# GPIO.net
KiCad netlist of a schematic drawn in Altium Designer
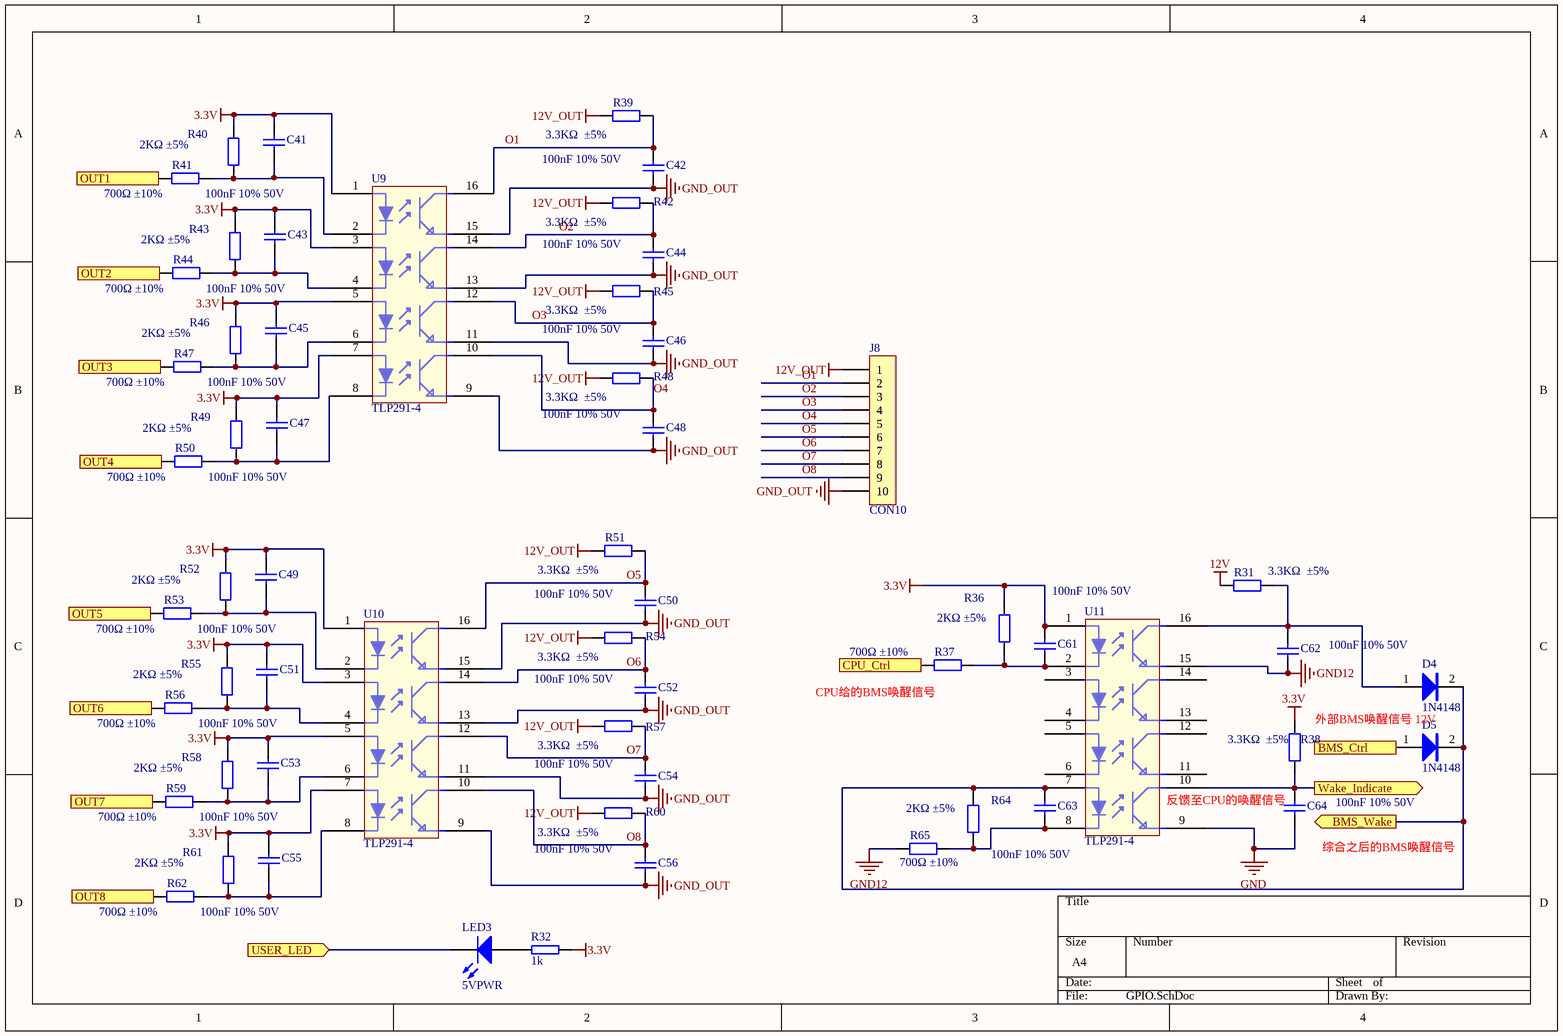
[diagram p0: GPIO.SchDoc]

(export (version "E")
  (design (tool "Eeschema 10.0.6"))
  (components
    (comp (ref "C41")
      (value "100nF 10% 50V")
      (footprint "0603_C")
      (description "贴片电容")
      (libsource (lib "Miscellaneous Devices LC") (part "0603 1nF (102) 10% 50V"))
    )
    (comp (ref "C42")
      (value "100nF 10% 50V")
      (footprint "0603_C")
      (description "贴片电容")
      (libsource (lib "Miscellaneous Devices LC") (part "0603 1nF (102) 10% 50V"))
    )
    (comp (ref "C43")
      (value "100nF 10% 50V")
      (footprint "0603_C")
      (description "贴片电容")
      (libsource (lib "Miscellaneous Devices LC") (part "0603 1nF (102) 10% 50V"))
    )
    (comp (ref "C44")
      (value "100nF 10% 50V")
      (footprint "0603_C")
      (description "贴片电容")
      (libsource (lib "Miscellaneous Devices LC") (part "0603 1nF (102) 10% 50V"))
    )
    (comp (ref "C45")
      (value "100nF 10% 50V")
      (footprint "0603_C")
      (description "贴片电容")
      (libsource (lib "Miscellaneous Devices LC") (part "0603 1nF (102) 10% 50V"))
    )
    (comp (ref "C46")
      (value "100nF 10% 50V")
      (footprint "0603_C")
      (description "贴片电容")
      (libsource (lib "Miscellaneous Devices LC") (part "0603 1nF (102) 10% 50V"))
    )
    (comp (ref "C47")
      (value "100nF 10% 50V")
      (footprint "0603_C")
      (description "贴片电容")
      (libsource (lib "Miscellaneous Devices LC") (part "0603 1nF (102) 10% 50V"))
    )
    (comp (ref "C48")
      (value "100nF 10% 50V")
      (footprint "0603_C")
      (description "贴片电容")
      (libsource (lib "Miscellaneous Devices LC") (part "0603 1nF (102) 10% 50V"))
    )
    (comp (ref "C49")
      (value "100nF 10% 50V")
      (footprint "0603_C")
      (description "贴片电容")
      (libsource (lib "Miscellaneous Devices LC") (part "0603 1nF (102) 10% 50V"))
    )
    (comp (ref "C50")
      (value "100nF 10% 50V")
      (footprint "0603_C")
      (description "贴片电容")
      (libsource (lib "Miscellaneous Devices LC") (part "0603 1nF (102) 10% 50V"))
    )
    (comp (ref "C51")
      (value "100nF 10% 50V")
      (footprint "0603_C")
      (description "贴片电容")
      (libsource (lib "Miscellaneous Devices LC") (part "0603 1nF (102) 10% 50V"))
    )
    (comp (ref "C52")
      (value "100nF 10% 50V")
      (footprint "0603_C")
      (description "贴片电容")
      (libsource (lib "Miscellaneous Devices LC") (part "0603 1nF (102) 10% 50V"))
    )
    (comp (ref "C53")
      (value "100nF 10% 50V")
      (footprint "0603_C")
      (description "贴片电容")
      (libsource (lib "Miscellaneous Devices LC") (part "0603 1nF (102) 10% 50V"))
    )
    (comp (ref "C54")
      (value "100nF 10% 50V")
      (footprint "0603_C")
      (description "贴片电容")
      (libsource (lib "Miscellaneous Devices LC") (part "0603 1nF (102) 10% 50V"))
    )
    (comp (ref "C55")
      (value "100nF 10% 50V")
      (footprint "0603_C")
      (description "贴片电容")
      (libsource (lib "Miscellaneous Devices LC") (part "0603 1nF (102) 10% 50V"))
    )
    (comp (ref "C56")
      (value "100nF 10% 50V")
      (footprint "0603_C")
      (description "贴片电容")
      (libsource (lib "Miscellaneous Devices LC") (part "0603 1nF (102) 10% 50V"))
    )
    (comp (ref "C61")
      (value "100nF 10% 50V")
      (footprint "0603_C")
      (description "贴片电容")
      (libsource (lib "Miscellaneous Devices LC") (part "0603 1nF (102) 10% 50V"))
    )
    (comp (ref "C62")
      (value "100nF 10% 50V")
      (footprint "0603_C")
      (description "贴片电容")
      (libsource (lib "Miscellaneous Devices LC") (part "0603 1nF (102) 10% 50V"))
    )
    (comp (ref "C63")
      (value "100nF 10% 50V")
      (footprint "0603_C")
      (description "贴片电容")
      (libsource (lib "Miscellaneous Devices LC") (part "0603 1nF (102) 10% 50V"))
    )
    (comp (ref "C64")
      (value "100nF 10% 50V")
      (footprint "0603_C")
      (description "贴片电容")
      (libsource (lib "Miscellaneous Devices LC") (part "0603 1nF (102) 10% 50V"))
    )
    (comp (ref "D4") (value "1N4148") (footprint "SOD-323") (libsource (lib "CORE") (part "SS34")))
    (comp (ref "D5") (value "1N4148") (footprint "SOD-323") (libsource (lib "CORE") (part "SS34")))
    (comp (ref "J8") (value "CON10") (footprint "XH2.54-SMD-5*2P") (libsource (lib "常用元件库") (part "CON10")))
    (comp (ref "LED3")
      (value "5VPWR")
      (footprint "LED")
      (description "Typical RED, GREEN, YELLOW, AMBER GaAs LED")
      (fields (field (name "PUBLISHER") "Altium Limited"))
      (libsource (lib "CORE") (part "LED2"))
    )
    (comp (ref "R31")
      (value "3.3KΩ  ±5%")
      (footprint "0603_R")
      (description "贴片电阻")
      (libsource (lib "") (part "0603 3.3KΩ (3301) 1%_1"))
    )
    (comp (ref "R32") (value "1k") (footprint "0603_R") (libsource (lib "EC20-北极芯") (part "RES")))
    (comp (ref "R36")
      (value "2KΩ ±5%")
      (footprint "0603_R")
      (description "贴片电阻")
      (libsource (lib "Miscellaneous Devices LC") (part "0603 2KΩ (2001) 1%"))
    )
    (comp (ref "R37")
      (value "700Ω ±10%")
      (footprint "0603_R")
      (description "贴片电阻")
      (libsource (lib "Miscellaneous Devices LC") (part "0603 5.6KΩ (5601) 1%"))
    )
    (comp (ref "R38")
      (value "3.3KΩ  ±5%")
      (footprint "0603_R")
      (description "贴片电阻")
      (libsource (lib "Miscellaneous Devices LC") (part "0603 3.3KΩ (3301) 1%"))
    )
    (comp (ref "R39")
      (value "3.3KΩ  ±5%")
      (footprint "0603_R")
      (description "贴片电阻")
      (libsource (lib "") (part "0603 3.3KΩ (3301) 1%_1"))
    )
    (comp (ref "R40")
      (value "2KΩ ±5%")
      (footprint "0603_R")
      (description "贴片电阻")
      (libsource (lib "Miscellaneous Devices LC") (part "0603 2KΩ (2001) 1%"))
    )
    (comp (ref "R41")
      (value "700Ω ±10%")
      (footprint "0603_R")
      (description "贴片电阻")
      (libsource (lib "Miscellaneous Devices LC") (part "0603 5.6KΩ (5601) 1%"))
    )
    (comp (ref "R42")
      (value "3.3KΩ  ±5%")
      (footprint "0603_R")
      (description "贴片电阻")
      (libsource (lib "") (part "0603 3.3KΩ (3301) 1%_1"))
    )
    (comp (ref "R43")
      (value "2KΩ ±5%")
      (footprint "0603_R")
      (description "贴片电阻")
      (libsource (lib "Miscellaneous Devices LC") (part "0603 2KΩ (2001) 1%"))
    )
    (comp (ref "R44")
      (value "700Ω ±10%")
      (footprint "0603_R")
      (description "贴片电阻")
      (libsource (lib "Miscellaneous Devices LC") (part "0603 5.6KΩ (5601) 1%"))
    )
    (comp (ref "R45")
      (value "3.3KΩ  ±5%")
      (footprint "0603_R")
      (description "贴片电阻")
      (libsource (lib "") (part "0603 3.3KΩ (3301) 1%_1"))
    )
    (comp (ref "R46")
      (value "2KΩ ±5%")
      (footprint "0603_R")
      (description "贴片电阻")
      (libsource (lib "Miscellaneous Devices LC") (part "0603 2KΩ (2001) 1%"))
    )
    (comp (ref "R47")
      (value "700Ω ±10%")
      (footprint "0603_R")
      (description "贴片电阻")
      (libsource (lib "Miscellaneous Devices LC") (part "0603 5.6KΩ (5601) 1%"))
    )
    (comp (ref "R48")
      (value "3.3KΩ  ±5%")
      (footprint "0603_R")
      (description "贴片电阻")
      (libsource (lib "") (part "0603 3.3KΩ (3301) 1%_1"))
    )
    (comp (ref "R49")
      (value "2KΩ ±5%")
      (footprint "0603_R")
      (description "贴片电阻")
      (libsource (lib "Miscellaneous Devices LC") (part "0603 2KΩ (2001) 1%"))
    )
    (comp (ref "R50")
      (value "700Ω ±10%")
      (footprint "0603_R")
      (description "贴片电阻")
      (libsource (lib "Miscellaneous Devices LC") (part "0603 5.6KΩ (5601) 1%"))
    )
    (comp (ref "R51")
      (value "3.3KΩ  ±5%")
      (footprint "0603_R")
      (description "贴片电阻")
      (libsource (lib "") (part "0603 3.3KΩ (3301) 1%_1"))
    )
    (comp (ref "R52")
      (value "2KΩ ±5%")
      (footprint "0603_R")
      (description "贴片电阻")
      (libsource (lib "Miscellaneous Devices LC") (part "0603 2KΩ (2001) 1%"))
    )
    (comp (ref "R53")
      (value "700Ω ±10%")
      (footprint "0603_R")
      (description "贴片电阻")
      (libsource (lib "Miscellaneous Devices LC") (part "0603 5.6KΩ (5601) 1%"))
    )
    (comp (ref "R54")
      (value "3.3KΩ  ±5%")
      (footprint "0603_R")
      (description "贴片电阻")
      (libsource (lib "") (part "0603 3.3KΩ (3301) 1%_1"))
    )
    (comp (ref "R55")
      (value "2KΩ ±5%")
      (footprint "0603_R")
      (description "贴片电阻")
      (libsource (lib "Miscellaneous Devices LC") (part "0603 2KΩ (2001) 1%"))
    )
    (comp (ref "R56")
      (value "700Ω ±10%")
      (footprint "0603_R")
      (description "贴片电阻")
      (libsource (lib "Miscellaneous Devices LC") (part "0603 5.6KΩ (5601) 1%"))
    )
    (comp (ref "R57")
      (value "3.3KΩ  ±5%")
      (footprint "0603_R")
      (description "贴片电阻")
      (libsource (lib "") (part "0603 3.3KΩ (3301) 1%_1"))
    )
    (comp (ref "R58")
      (value "2KΩ ±5%")
      (footprint "0603_R")
      (description "贴片电阻")
      (libsource (lib "Miscellaneous Devices LC") (part "0603 2KΩ (2001) 1%"))
    )
    (comp (ref "R59")
      (value "700Ω ±10%")
      (footprint "0603_R")
      (description "贴片电阻")
      (libsource (lib "Miscellaneous Devices LC") (part "0603 5.6KΩ (5601) 1%"))
    )
    (comp (ref "R60")
      (value "3.3KΩ  ±5%")
      (footprint "0603_R")
      (description "贴片电阻")
      (libsource (lib "") (part "0603 3.3KΩ (3301) 1%_1"))
    )
    (comp (ref "R61")
      (value "2KΩ ±5%")
      (footprint "0603_R")
      (description "贴片电阻")
      (libsource (lib "Miscellaneous Devices LC") (part "0603 2KΩ (2001) 1%"))
    )
    (comp (ref "R62")
      (value "700Ω ±10%")
      (footprint "0603_R")
      (description "贴片电阻")
      (libsource (lib "Miscellaneous Devices LC") (part "0603 5.6KΩ (5601) 1%"))
    )
    (comp (ref "R64")
      (value "2KΩ ±5%")
      (footprint "0603_R")
      (description "贴片电阻")
      (libsource (lib "Miscellaneous Devices LC") (part "0603 2KΩ (2001) 1%"))
    )
    (comp (ref "R65")
      (value "700Ω ±10%")
      (footprint "0603_R")
      (description "贴片电阻")
      (libsource (lib "Miscellaneous Devices LC") (part "0603 5.6KΩ (5601) 1%"))
    )
    (comp (ref "U9")
      (value "TLP291-4")
      (footprint "SOP16_M")
      (description "东芝四通道光耦 SOP16")
      (libsource (lib "LINXUE") (part "PS2801"))
    )
    (comp (ref "U10")
      (value "TLP291-4")
      (footprint "SOP16_M")
      (description "东芝四通道光耦 SOP16")
      (libsource (lib "LINXUE") (part "PS2801"))
    )
    (comp (ref "U11")
      (value "TLP291-4")
      (footprint "SOP16_M")
      (description "东芝四通道光耦 SOP16")
      (libsource (lib "LINXUE") (part "PS2801"))
    )
  )
  (nets
    (net (code "1") (name "/BMS_Ctrl") (class "Default")
      (node (ref "D5") (pin "1") (pinfunction "1_1") (pintype "passive"))
    )
    (net (code "2") (name "/BMS_Wake") (class "Default")
      (node (ref "C63") (pin "2") (pinfunction "2_2") (pintype "passive"))
      (node (ref "D4") (pin "2") (pinfunction "2_2") (pintype "passive"))
      (node (ref "D5") (pin "2") (pinfunction "2_2") (pintype "passive"))
      (node (ref "R64") (pin "2") (pinfunction "2_2") (pintype "passive"))
      (node (ref "U11") (pin "7") (pinfunction "7_7") (pintype "passive"))
    )
    (net (code "3") (name "/CPU_Ctrl") (class "Default")
      (node (ref "R37") (pin "1") (pinfunction "1_1") (pintype "passive"))
    )
    (net (code "4") (name "/O1") (class "Default")
      (node (ref "C42") (pin "2") (pinfunction "2_2") (pintype "passive"))
      (node (ref "J8") (pin "2") (pinfunction "2_2") (pintype "passive"))
      (node (ref "R39") (pin "1") (pinfunction "1_1") (pintype "passive"))
      (node (ref "U9") (pin "16") (pinfunction "16_16") (pintype "passive"))
    )
    (net (code "5") (name "/O2") (class "Default")
      (node (ref "C44") (pin "2") (pinfunction "2_2") (pintype "passive"))
      (node (ref "J8") (pin "3") (pinfunction "3_3") (pintype "passive"))
      (node (ref "R42") (pin "1") (pinfunction "1_1") (pintype "passive"))
      (node (ref "U9") (pin "14") (pinfunction "14_14") (pintype "passive"))
    )
    (net (code "6") (name "/O3") (class "Default")
      (node (ref "C46") (pin "2") (pinfunction "2_2") (pintype "passive"))
      (node (ref "J8") (pin "4") (pinfunction "4_4") (pintype "passive"))
      (node (ref "R45") (pin "1") (pinfunction "1_1") (pintype "passive"))
      (node (ref "U9") (pin "12") (pinfunction "12_12") (pintype "passive"))
    )
    (net (code "7") (name "/O4") (class "Default")
      (node (ref "C48") (pin "2") (pinfunction "2_2") (pintype "passive"))
      (node (ref "J8") (pin "5") (pinfunction "5_5") (pintype "passive"))
      (node (ref "R48") (pin "1") (pinfunction "1_1") (pintype "passive"))
      (node (ref "U9") (pin "10") (pinfunction "10_10") (pintype "passive"))
    )
    (net (code "8") (name "/O5") (class "Default")
      (node (ref "C50") (pin "2") (pinfunction "2_2") (pintype "passive"))
      (node (ref "J8") (pin "6") (pinfunction "6_6") (pintype "passive"))
      (node (ref "R51") (pin "1") (pinfunction "1_1") (pintype "passive"))
      (node (ref "U10") (pin "16") (pinfunction "16_16") (pintype "passive"))
    )
    (net (code "9") (name "/O6") (class "Default")
      (node (ref "C52") (pin "2") (pinfunction "2_2") (pintype "passive"))
      (node (ref "J8") (pin "7") (pinfunction "7_7") (pintype "passive"))
      (node (ref "R54") (pin "1") (pinfunction "1_1") (pintype "passive"))
      (node (ref "U10") (pin "14") (pinfunction "14_14") (pintype "passive"))
    )
    (net (code "10") (name "/O7") (class "Default")
      (node (ref "C54") (pin "2") (pinfunction "2_2") (pintype "passive"))
      (node (ref "J8") (pin "8") (pinfunction "8_8") (pintype "passive"))
      (node (ref "R57") (pin "1") (pinfunction "1_1") (pintype "passive"))
      (node (ref "U10") (pin "12") (pinfunction "12_12") (pintype "passive"))
    )
    (net (code "11") (name "/O8") (class "Default")
      (node (ref "C56") (pin "2") (pinfunction "2_2") (pintype "passive"))
      (node (ref "J8") (pin "9") (pinfunction "9_9") (pintype "passive"))
      (node (ref "R60") (pin "1") (pinfunction "1_1") (pintype "passive"))
      (node (ref "U10") (pin "10") (pinfunction "10_10") (pintype "passive"))
    )
    (net (code "12") (name "/OUT1") (class "Default")
      (node (ref "R41") (pin "1") (pinfunction "1_1") (pintype "passive"))
    )
    (net (code "13") (name "/OUT2") (class "Default")
      (node (ref "R44") (pin "1") (pinfunction "1_1") (pintype "passive"))
    )
    (net (code "14") (name "/OUT3") (class "Default")
      (node (ref "R47") (pin "1") (pinfunction "1_1") (pintype "passive"))
    )
    (net (code "15") (name "/OUT4") (class "Default")
      (node (ref "R50") (pin "1") (pinfunction "1_1") (pintype "passive"))
    )
    (net (code "16") (name "/OUT5") (class "Default")
      (node (ref "R53") (pin "1") (pinfunction "1_1") (pintype "passive"))
    )
    (net (code "17") (name "/OUT6") (class "Default")
      (node (ref "R56") (pin "1") (pinfunction "1_1") (pintype "passive"))
    )
    (net (code "18") (name "/OUT7") (class "Default")
      (node (ref "R59") (pin "1") (pinfunction "1_1") (pintype "passive"))
    )
    (net (code "19") (name "/OUT8") (class "Default")
      (node (ref "R62") (pin "1") (pinfunction "1_1") (pintype "passive"))
    )
    (net (code "20") (name "/USER_LED") (class "Default")
      (node (ref "LED3") (pin "2") (pinfunction "K_2") (pintype "passive"))
    )
    (net (code "21") (name "/Wake_Indicate") (class "Default")
      (node (ref "C64") (pin "2") (pinfunction "2_2") (pintype "passive"))
      (node (ref "R38") (pin "2") (pinfunction "2_2") (pintype "passive"))
      (node (ref "U11") (pin "10") (pinfunction "10_10") (pintype "passive"))
    )
    (net (code "22") (name "3.3V") (class "Default")
      (node (ref "C41") (pin "2") (pinfunction "2_2") (pintype "passive"))
      (node (ref "C43") (pin "2") (pinfunction "2_2") (pintype "passive"))
      (node (ref "C45") (pin "2") (pinfunction "2_2") (pintype "passive"))
      (node (ref "C47") (pin "2") (pinfunction "2_2") (pintype "passive"))
      (node (ref "C49") (pin "2") (pinfunction "2_2") (pintype "passive"))
      (node (ref "C51") (pin "2") (pinfunction "2_2") (pintype "passive"))
      (node (ref "C53") (pin "2") (pinfunction "2_2") (pintype "passive"))
      (node (ref "C55") (pin "2") (pinfunction "2_2") (pintype "passive"))
      (node (ref "C61") (pin "2") (pinfunction "2_2") (pintype "passive"))
      (node (ref "R32") (pin "1") (pinfunction "1_1") (pintype "passive"))
      (node (ref "R36") (pin "2") (pinfunction "2_2") (pintype "passive"))
      (node (ref "R38") (pin "1") (pinfunction "1_1") (pintype "passive"))
      (node (ref "R40") (pin "2") (pinfunction "2_2") (pintype "passive"))
      (node (ref "R43") (pin "2") (pinfunction "2_2") (pintype "passive"))
      (node (ref "R46") (pin "2") (pinfunction "2_2") (pintype "passive"))
      (node (ref "R49") (pin "2") (pinfunction "2_2") (pintype "passive"))
      (node (ref "R52") (pin "2") (pinfunction "2_2") (pintype "passive"))
      (node (ref "R55") (pin "2") (pinfunction "2_2") (pintype "passive"))
      (node (ref "R58") (pin "2") (pinfunction "2_2") (pintype "passive"))
      (node (ref "R61") (pin "2") (pinfunction "2_2") (pintype "passive"))
      (node (ref "U10") (pin "1") (pinfunction "INPUT-A_1") (pintype "passive"))
      (node (ref "U10") (pin "3") (pinfunction "EMITTER_3") (pintype "passive"))
      (node (ref "U10") (pin "5") (pinfunction "5_5") (pintype "passive"))
      (node (ref "U10") (pin "7") (pinfunction "7_7") (pintype "passive"))
      (node (ref "U11") (pin "1") (pinfunction "INPUT-A_1") (pintype "passive"))
      (node (ref "U9") (pin "1") (pinfunction "INPUT-A_1") (pintype "passive"))
      (node (ref "U9") (pin "3") (pinfunction "EMITTER_3") (pintype "passive"))
      (node (ref "U9") (pin "5") (pinfunction "5_5") (pintype "passive"))
      (node (ref "U9") (pin "7") (pinfunction "7_7") (pintype "passive"))
    )
    (net (code "23") (name "12V") (class "Default")
      (node (ref "R31") (pin "2") (pinfunction "2_2") (pintype "passive"))
    )
    (net (code "24") (name "12V_OUT") (class "Default")
      (node (ref "J8") (pin "1") (pinfunction "1_1") (pintype "passive"))
      (node (ref "R39") (pin "2") (pinfunction "2_2") (pintype "passive"))
      (node (ref "R42") (pin "2") (pinfunction "2_2") (pintype "passive"))
      (node (ref "R45") (pin "2") (pinfunction "2_2") (pintype "passive"))
      (node (ref "R48") (pin "2") (pinfunction "2_2") (pintype "passive"))
      (node (ref "R51") (pin "2") (pinfunction "2_2") (pintype "passive"))
      (node (ref "R54") (pin "2") (pinfunction "2_2") (pintype "passive"))
      (node (ref "R57") (pin "2") (pinfunction "2_2") (pintype "passive"))
      (node (ref "R60") (pin "2") (pinfunction "2_2") (pintype "passive"))
    )
    (net (code "25") (name "GND") (class "Default")
      (node (ref "C64") (pin "1") (pinfunction "1_1") (pintype "passive"))
      (node (ref "U11") (pin "9") (pinfunction "9_9") (pintype "passive"))
    )
    (net (code "26") (name "GND12") (class "Default")
      (node (ref "C62") (pin "1") (pinfunction "1_1") (pintype "passive"))
      (node (ref "R65") (pin "1") (pinfunction "1_1") (pintype "passive"))
      (node (ref "U11") (pin "15") (pinfunction "15_15") (pintype "passive"))
    )
    (net (code "27") (name "GND_OUT") (class "Default")
      (node (ref "C42") (pin "1") (pinfunction "1_1") (pintype "passive"))
      (node (ref "C44") (pin "1") (pinfunction "1_1") (pintype "passive"))
      (node (ref "C46") (pin "1") (pinfunction "1_1") (pintype "passive"))
      (node (ref "C48") (pin "1") (pinfunction "1_1") (pintype "passive"))
      (node (ref "C50") (pin "1") (pinfunction "1_1") (pintype "passive"))
      (node (ref "C52") (pin "1") (pinfunction "1_1") (pintype "passive"))
      (node (ref "C54") (pin "1") (pinfunction "1_1") (pintype "passive"))
      (node (ref "C56") (pin "1") (pinfunction "1_1") (pintype "passive"))
      (node (ref "J8") (pin "10") (pinfunction "10_10") (pintype "passive"))
      (node (ref "U10") (pin "11") (pinfunction "11_11") (pintype "passive"))
      (node (ref "U10") (pin "13") (pinfunction "13_13") (pintype "passive"))
      (node (ref "U10") (pin "15") (pinfunction "15_15") (pintype "passive"))
      (node (ref "U10") (pin "9") (pinfunction "9_9") (pintype "passive"))
      (node (ref "U9") (pin "11") (pinfunction "11_11") (pintype "passive"))
      (node (ref "U9") (pin "13") (pinfunction "13_13") (pintype "passive"))
      (node (ref "U9") (pin "15") (pinfunction "15_15") (pintype "passive"))
      (node (ref "U9") (pin "9") (pinfunction "9_9") (pintype "passive"))
    )
    (net (code "28") (name "Net-(C45-Pad1)") (class "Default")
      (node (ref "C45") (pin "1") (pinfunction "1_1") (pintype "passive"))
      (node (ref "R46") (pin "1") (pinfunction "1_1") (pintype "passive"))
      (node (ref "R47") (pin "2") (pinfunction "2_2") (pintype "passive"))
      (node (ref "U9") (pin "6") (pinfunction "6_6") (pintype "passive"))
    )
    (net (code "29") (name "Net-(C47-Pad1)") (class "Default")
      (node (ref "C47") (pin "1") (pinfunction "1_1") (pintype "passive"))
      (node (ref "R49") (pin "1") (pinfunction "1_1") (pintype "passive"))
      (node (ref "R50") (pin "2") (pinfunction "2_2") (pintype "passive"))
      (node (ref "U9") (pin "8") (pinfunction "8_8") (pintype "passive"))
    )
    (net (code "30") (name "Net-(C53-Pad1)") (class "Default")
      (node (ref "C53") (pin "1") (pinfunction "1_1") (pintype "passive"))
      (node (ref "R58") (pin "1") (pinfunction "1_1") (pintype "passive"))
      (node (ref "R59") (pin "2") (pinfunction "2_2") (pintype "passive"))
      (node (ref "U10") (pin "6") (pinfunction "6_6") (pintype "passive"))
    )
    (net (code "31") (name "Net-(C55-Pad1)") (class "Default")
      (node (ref "C55") (pin "1") (pinfunction "1_1") (pintype "passive"))
      (node (ref "R61") (pin "1") (pinfunction "1_1") (pintype "passive"))
      (node (ref "R62") (pin "2") (pinfunction "2_2") (pintype "passive"))
      (node (ref "U10") (pin "8") (pinfunction "8_8") (pintype "passive"))
    )
    (net (code "32") (name "Net-(C62-Pad2)") (class "Default")
      (node (ref "C62") (pin "2") (pinfunction "2_2") (pintype "passive"))
      (node (ref "D4") (pin "1") (pinfunction "1_1") (pintype "passive"))
      (node (ref "R31") (pin "1") (pinfunction "1_1") (pintype "passive"))
      (node (ref "U11") (pin "16") (pinfunction "16_16") (pintype "passive"))
    )
    (net (code "33") (name "Net-(C63-Pad1)") (class "Default")
      (node (ref "C63") (pin "1") (pinfunction "1_1") (pintype "passive"))
      (node (ref "R64") (pin "1") (pinfunction "1_1") (pintype "passive"))
      (node (ref "R65") (pin "2") (pinfunction "2_2") (pintype "passive"))
      (node (ref "U11") (pin "8") (pinfunction "8_8") (pintype "passive"))
    )
    (net (code "34") (name "Net-(LED3-A)") (class "Default")
      (node (ref "LED3") (pin "1") (pinfunction "A_1") (pintype "passive"))
      (node (ref "R32") (pin "2") (pinfunction "2_2") (pintype "passive"))
    )
    (net (code "35") (name "Net-(U9-COLLECTOR)") (class "Default")
      (node (ref "C43") (pin "1") (pinfunction "1_1") (pintype "passive"))
      (node (ref "R43") (pin "1") (pinfunction "1_1") (pintype "passive"))
      (node (ref "R44") (pin "2") (pinfunction "2_2") (pintype "passive"))
      (node (ref "U9") (pin "4") (pinfunction "COLLECTOR_4") (pintype "open_collector"))
    )
    (net (code "36") (name "Net-(U9-INPUT-K)") (class "Default")
      (node (ref "C41") (pin "1") (pinfunction "1_1") (pintype "passive"))
      (node (ref "R40") (pin "1") (pinfunction "1_1") (pintype "passive"))
      (node (ref "R41") (pin "2") (pinfunction "2_2") (pintype "passive"))
      (node (ref "U9") (pin "2") (pinfunction "INPUT-K_2") (pintype "passive"))
    )
    (net (code "37") (name "Net-(U10-COLLECTOR)") (class "Default")
      (node (ref "C51") (pin "1") (pinfunction "1_1") (pintype "passive"))
      (node (ref "R55") (pin "1") (pinfunction "1_1") (pintype "passive"))
      (node (ref "R56") (pin "2") (pinfunction "2_2") (pintype "passive"))
      (node (ref "U10") (pin "4") (pinfunction "COLLECTOR_4") (pintype "open_collector"))
    )
    (net (code "38") (name "Net-(U10-INPUT-K)") (class "Default")
      (node (ref "C49") (pin "1") (pinfunction "1_1") (pintype "passive"))
      (node (ref "R52") (pin "1") (pinfunction "1_1") (pintype "passive"))
      (node (ref "R53") (pin "2") (pinfunction "2_2") (pintype "passive"))
      (node (ref "U10") (pin "2") (pinfunction "INPUT-K_2") (pintype "passive"))
    )
    (net (code "39") (name "Net-(U11-INPUT-K)") (class "Default")
      (node (ref "C61") (pin "1") (pinfunction "1_1") (pintype "passive"))
      (node (ref "R36") (pin "1") (pinfunction "1_1") (pintype "passive"))
      (node (ref "R37") (pin "2") (pinfunction "2_2") (pintype "passive"))
      (node (ref "U11") (pin "2") (pinfunction "INPUT-K_2") (pintype "passive"))
    )
    (net (code "40") (name "unconnected-(U11-COLLECTOR-Pad4)") (class "Default")
      (node (ref "U11") (pin "4") (pinfunction "COLLECTOR_4") (pintype "open_collector"))
    )
    (net (code "41") (name "unconnected-(U11-EMITTER-Pad3)") (class "Default")
      (node (ref "U11") (pin "3") (pinfunction "EMITTER_3") (pintype "passive"))
    )
    (net (code "42") (name "unconnected-(U11-Pad5)") (class "Default")
      (node (ref "U11") (pin "5") (pinfunction "5_5") (pintype "passive"))
    )
    (net (code "43") (name "unconnected-(U11-Pad6)") (class "Default")
      (node (ref "U11") (pin "6") (pinfunction "6_6") (pintype "passive"))
    )
    (net (code "44") (name "unconnected-(U11-Pad11)") (class "Default")
      (node (ref "U11") (pin "11") (pinfunction "11_11") (pintype "passive"))
    )
    (net (code "45") (name "unconnected-(U11-Pad12)") (class "Default")
      (node (ref "U11") (pin "12") (pinfunction "12_12") (pintype "passive"))
    )
    (net (code "46") (name "unconnected-(U11-Pad13)") (class "Default")
      (node (ref "U11") (pin "13") (pinfunction "13_13") (pintype "passive"))
    )
    (net (code "47") (name "unconnected-(U11-Pad14)") (class "Default")
      (node (ref "U11") (pin "14") (pinfunction "14_14") (pintype "passive"))
    )
  )
)
